# 5_ButtonsAndLeds.net
KiCad netlist of a schematic drawn in Altium Designer
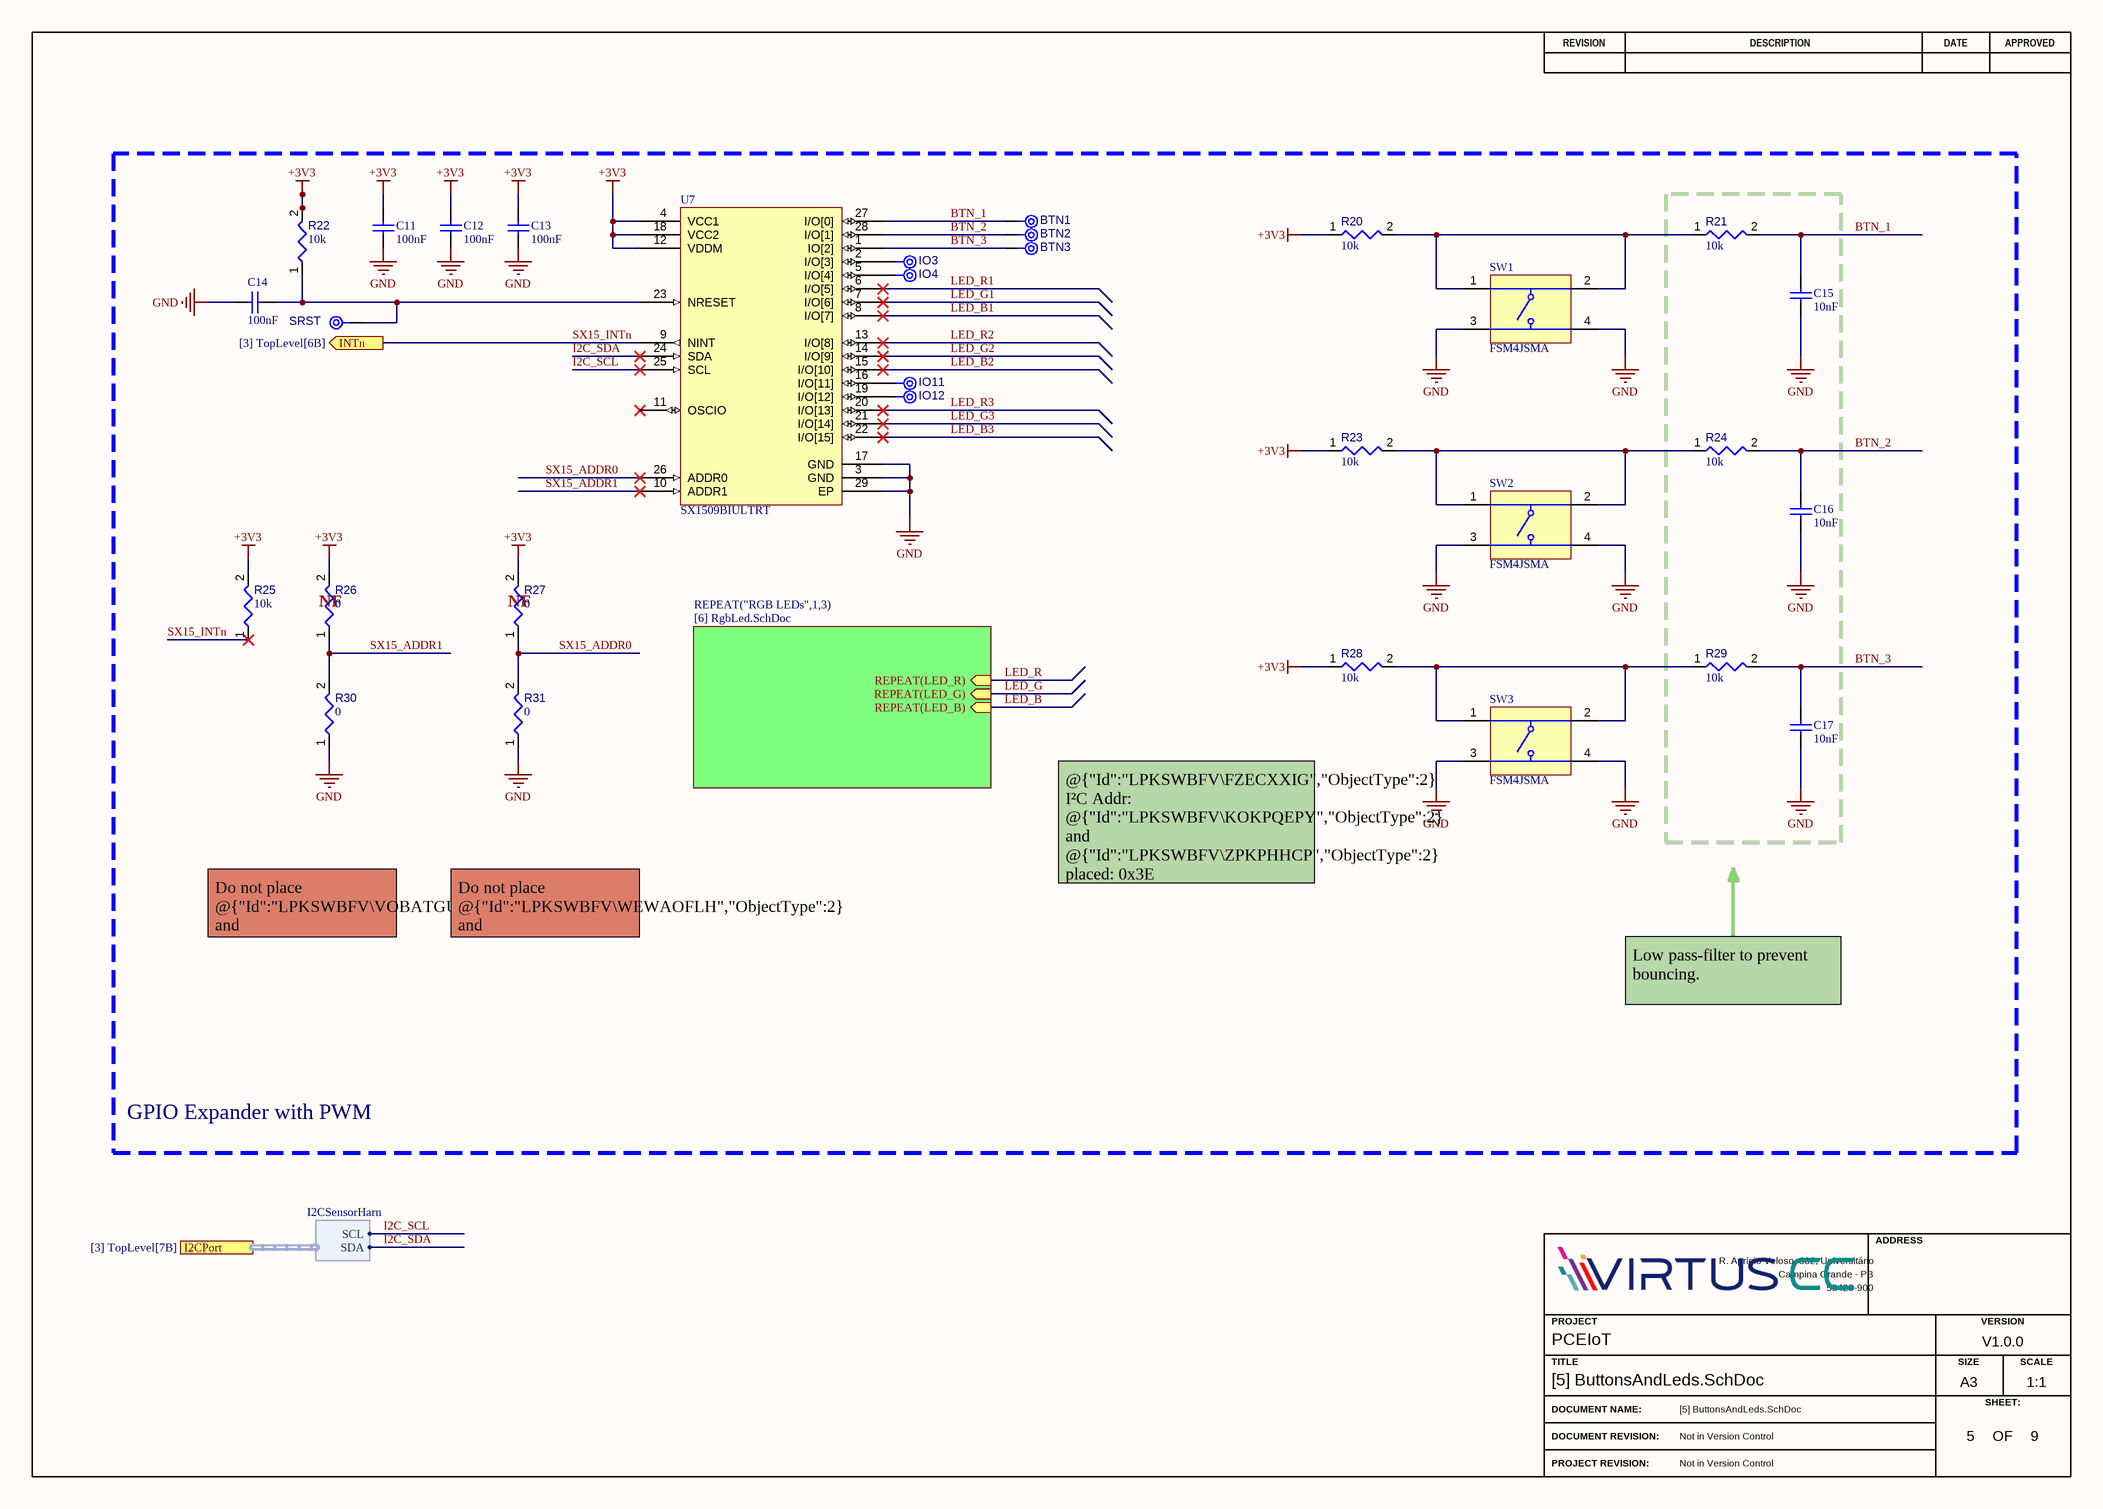
[diagram p0: [5] ButtonsAndLeds.SchDoc]

(export (version "E")
  (design (tool "Eeschema 10.0.6"))
  (components
    (comp (ref "BTN1")
      (value "TPAD6R")
      (footprint "TP06R")
      (description "0.6mm round")
      (libsource (lib "PCEIOT") (part "CMP-00028-00002-2"))
    )
    (comp (ref "BTN2")
      (value "TPAD6R")
      (footprint "TP06R")
      (description "0.6mm round")
      (libsource (lib "PCEIOT") (part "CMP-00028-00002-2"))
    )
    (comp (ref "BTN3")
      (value "TPAD6R")
      (footprint "TP06R")
      (description "0.6mm round")
      (libsource (lib "PCEIOT") (part "CMP-00028-00002-2"))
    )
    (comp (ref "C11")
      (value "100nF")
      (footprint "CAPC0603(1608)100_L")
      (description "Multilayer Ceramic Capacitor, 0.1 uF, 16 V, ± 20%, X7R, 0603 [1608 Metric]")
      (fields (field (name "TOLERANCE") "20%") (field (name "Comment") "VJ0603Y104MXJCW1BC"))
      (libsource (lib "UFCG - Universidade Federal de Campina Grande") (part "CAP"))
    )
    (comp (ref "C12")
      (value "100nF")
      (footprint "CAPC0603(1608)100_L")
      (description "Multilayer Ceramic Capacitor, 0.1 uF, 16 V, ± 20%, X7R, 0603 [1608 Metric]")
      (fields (field (name "TOLERANCE") "20%") (field (name "Comment") "VJ0603Y104MXJCW1BC"))
      (libsource (lib "UFCG - Universidade Federal de Campina Grande") (part "CAP"))
    )
    (comp (ref "C13")
      (value "100nF")
      (footprint "CAPC0603(1608)100_L")
      (description "Multilayer Ceramic Capacitor, 0.1 uF, 16 V, ± 20%, X7R, 0603 [1608 Metric]")
      (fields (field (name "TOLERANCE") "20%") (field (name "Comment") "VJ0603Y104MXJCW1BC"))
      (libsource (lib "UFCG - Universidade Federal de Campina Grande") (part "CAP"))
    )
    (comp (ref "C14")
      (value "100nF")
      (footprint "CAPC0603(1608)100_L")
      (description "Multilayer Ceramic Capacitor, 0.1 uF, 16 V, ± 20%, X7R, 0603 [1608 Metric]")
      (fields (field (name "TOLERANCE") "20%") (field (name "Comment") "VJ0603Y104MXJCW1BC"))
      (libsource (lib "UFCG - Universidade Federal de Campina Grande") (part "CAP"))
    )
    (comp (ref "C15")
      (value "10nF")
      (footprint "CAPC0603(1608)100_L")
      (description "Multilayer Ceramic Capacitor, 0.01 uF, 50 V, ± 10%, X7R, 0603 [1608 Metric]")
      (fields (field (name "VOLTAGE") "50V") (field (name "TOLERANCE") "10%"))
      (libsource (lib "UFCG - Universidade Federal de Campina Grande") (part "CAP"))
    )
    (comp (ref "C16")
      (value "10nF")
      (footprint "CAPC0603(1608)100_L")
      (description "Multilayer Ceramic Capacitor, 0.01 uF, 50 V, ± 10%, X7R, 0603 [1608 Metric]")
      (fields (field (name "VOLTAGE") "50V") (field (name "TOLERANCE") "10%"))
      (libsource (lib "UFCG - Universidade Federal de Campina Grande") (part "CAP"))
    )
    (comp (ref "C17")
      (value "10nF")
      (footprint "CAPC0603(1608)100_L")
      (description "Multilayer Ceramic Capacitor, 0.01 uF, 50 V, ± 10%, X7R, 0603 [1608 Metric]")
      (fields (field (name "VOLTAGE") "50V") (field (name "TOLERANCE") "10%"))
      (libsource (lib "UFCG - Universidade Federal de Campina Grande") (part "CAP"))
    )
    (comp (ref "IO3")
      (value "TPAD6R")
      (footprint "TP06R")
      (description "0.6mm round")
      (libsource (lib "PCEIOT") (part "CMP-00028-00002-2"))
    )
    (comp (ref "IO4")
      (value "TPAD6R")
      (footprint "TP06R")
      (description "0.6mm round")
      (libsource (lib "PCEIOT") (part "CMP-00028-00002-2"))
    )
    (comp (ref "IO11")
      (value "TPAD6R")
      (footprint "TP06R")
      (description "0.6mm round")
      (libsource (lib "PCEIOT") (part "CMP-00028-00002-2"))
    )
    (comp (ref "IO12")
      (value "TPAD6R")
      (footprint "TP06R")
      (description "0.6mm round")
      (libsource (lib "PCEIOT") (part "CMP-00028-00002-2"))
    )
    (comp (ref "R20")
      (value "10k")
      (footprint "RESC0603(1608)_L")
      (description "Chip Resistor, 10 KOhm, +/- 1%, 01 W, -55 to 155 degC, 0603 (1608 Metric)")
      (fields (field (name "POWER") "100mW") (field (name "TOLERANCE") "1%"))
      (libsource (lib "UFCG - Universidade Federal de Campina Grande") (part "RES-2"))
    )
    (comp (ref "R21")
      (value "10k")
      (footprint "RESC0603(1608)_L")
      (description "Chip Resistor, 10 KOhm, +/- 1%, 01 W, -55 to 155 degC, 0603 (1608 Metric)")
      (fields (field (name "POWER") "100mW") (field (name "TOLERANCE") "1%"))
      (libsource (lib "UFCG - Universidade Federal de Campina Grande") (part "RES-2"))
    )
    (comp (ref "R22")
      (value "10k")
      (footprint "RESC0603(1608)_L")
      (description "Chip Resistor, 10 KOhm, +/- 1%, 01 W, -55 to 155 degC, 0603 (1608 Metric)")
      (fields (field (name "POWER") "100mW") (field (name "TOLERANCE") "1%"))
      (libsource (lib "UFCG - Universidade Federal de Campina Grande") (part "RES-2"))
    )
    (comp (ref "R23")
      (value "10k")
      (footprint "RESC0603(1608)_L")
      (description "Chip Resistor, 10 KOhm, +/- 1%, 01 W, -55 to 155 degC, 0603 (1608 Metric)")
      (fields (field (name "POWER") "100mW") (field (name "TOLERANCE") "1%"))
      (libsource (lib "UFCG - Universidade Federal de Campina Grande") (part "RES-2"))
    )
    (comp (ref "R24")
      (value "10k")
      (footprint "RESC0603(1608)_L")
      (description "Chip Resistor, 10 KOhm, +/- 1%, 01 W, -55 to 155 degC, 0603 (1608 Metric)")
      (fields (field (name "POWER") "100mW") (field (name "TOLERANCE") "1%"))
      (libsource (lib "UFCG - Universidade Federal de Campina Grande") (part "RES-2"))
    )
    (comp (ref "R25")
      (value "10k")
      (footprint "RESC0603(1608)_L")
      (description "Chip Resistor, 10 KOhm, +/- 1%, 01 W, -55 to 155 degC, 0603 (1608 Metric)")
      (fields (field (name "POWER") "100mW") (field (name "TOLERANCE") "1%"))
      (libsource (lib "UFCG - Universidade Federal de Campina Grande") (part "RES-2"))
    )
    (comp (ref "R26")
      (value "0")
      (footprint "RESC0603(1608)_L")
      (description "Chip Resistor, 0 Ohm, 0.1 W, -55 to 155 degC, 0603 (1608 Metric)")
      (fields (field (name "TOLERANCE") "5%") (field (name "POWER") "100mW"))
      (libsource (lib "UFCG - Universidade Federal de Campina Grande") (part "RES-2"))
    )
    (comp (ref "R27")
      (value "0")
      (footprint "RESC0603(1608)_L")
      (description "Chip Resistor, 0 Ohm, 0.1 W, -55 to 155 degC, 0603 (1608 Metric)")
      (fields (field (name "TOLERANCE") "5%") (field (name "POWER") "100mW"))
      (libsource (lib "UFCG - Universidade Federal de Campina Grande") (part "RES-2"))
    )
    (comp (ref "R28")
      (value "10k")
      (footprint "RESC0603(1608)_L")
      (description "Chip Resistor, 10 KOhm, +/- 1%, 01 W, -55 to 155 degC, 0603 (1608 Metric)")
      (fields (field (name "POWER") "100mW") (field (name "TOLERANCE") "1%"))
      (libsource (lib "UFCG - Universidade Federal de Campina Grande") (part "RES-2"))
    )
    (comp (ref "R29")
      (value "10k")
      (footprint "RESC0603(1608)_L")
      (description "Chip Resistor, 10 KOhm, +/- 1%, 01 W, -55 to 155 degC, 0603 (1608 Metric)")
      (fields (field (name "POWER") "100mW") (field (name "TOLERANCE") "1%"))
      (libsource (lib "UFCG - Universidade Federal de Campina Grande") (part "RES-2"))
    )
    (comp (ref "R30")
      (value "0")
      (footprint "RESC0603(1608)_L")
      (description "Chip Resistor, 0 Ohm, 0.1 W, -55 to 155 degC, 0603 (1608 Metric)")
      (fields (field (name "TOLERANCE") "5%") (field (name "POWER") "100mW"))
      (libsource (lib "UFCG - Universidade Federal de Campina Grande") (part "RES-2"))
    )
    (comp (ref "R31")
      (value "0")
      (footprint "RESC0603(1608)_L")
      (description "Chip Resistor, 0 Ohm, 0.1 W, -55 to 155 degC, 0603 (1608 Metric)")
      (fields (field (name "TOLERANCE") "5%") (field (name "POWER") "100mW"))
      (libsource (lib "UFCG - Universidade Federal de Campina Grande") (part "RES-2"))
    )
    (comp (ref "SRST")
      (value "TPAD6R")
      (footprint "TP06R")
      (description "0.6mm round")
      (libsource (lib "PCEIOT") (part "CMP-00028-00002-2"))
    )
    (comp (ref "SW1")
      (value "FSM4JSMA")
      (footprint "TECO-FSM4JSMA_V")
      (description "Switch Tactile OFF (ON) SPST Round Button Gull Wing 0.05A 12VDC 1.57N SMD Loose Piece")
      (libsource (lib "UFCG - Universidade Federal de Campina Grande") (part "SW-SPST-4_A"))
    )
    (comp (ref "SW2")
      (value "FSM4JSMA")
      (footprint "TECO-FSM4JSMA_V")
      (description "Switch Tactile OFF (ON) SPST Round Button Gull Wing 0.05A 12VDC 1.57N SMD Loose Piece")
      (libsource (lib "UFCG - Universidade Federal de Campina Grande") (part "SW-SPST-4_A"))
    )
    (comp (ref "SW3")
      (value "FSM4JSMA")
      (footprint "TECO-FSM4JSMA_V")
      (description "Switch Tactile OFF (ON) SPST Round Button Gull Wing 0.05A 12VDC 1.57N SMD Loose Piece")
      (libsource (lib "UFCG - Universidade Federal de Campina Grande") (part "SW-SPST-4_A"))
    )
    (comp (ref "U7")
      (value "SX1509BIULTRT")
      (footprint "QFN40P410X410X60_HS-29N")
      (description "IC Gpio Expander I2C 16CH 28QFN / I2C Interface 5.5V 28-PIN Qfn-ut Ep T/r")
      (libsource (lib "UFCG - Universidade Federal de Campina Grande") (part "New symbol 1"))
    )
  )
  (nets
    (net (code "2") (name "+3V3") (class "Default")
      (node (ref "C11") (pin "2") (pinfunction "2_2") (pintype "passive"))
      (node (ref "C12") (pin "2") (pinfunction "2_2") (pintype "passive"))
      (node (ref "C13") (pin "2") (pinfunction "2_2") (pintype "passive"))
      (node (ref "R20") (pin "1") (pinfunction "1_1") (pintype "passive"))
      (node (ref "R22") (pin "2") (pinfunction "2_2") (pintype "passive"))
      (node (ref "R23") (pin "1") (pinfunction "1_1") (pintype "passive"))
      (node (ref "R25") (pin "2") (pinfunction "2_2") (pintype "passive"))
      (node (ref "R26") (pin "2") (pinfunction "2_2") (pintype "passive"))
      (node (ref "R27") (pin "2") (pinfunction "2_2") (pintype "passive"))
      (node (ref "R28") (pin "1") (pinfunction "1_1") (pintype "passive"))
      (node (ref "U7") (pin "12") (pinfunction "VDDM_12") (pintype "power_in"))
      (node (ref "U7") (pin "18") (pinfunction "VCC2_18") (pintype "power_in"))
      (node (ref "U7") (pin "4") (pinfunction "VCC1_4") (pintype "power_in"))
    )
    (net (code "3") (name "/BTN_1") (class "Default")
      (node (ref "BTN1") (pin "1") (pinfunction "TP_1") (pintype "passive"))
      (node (ref "C15") (pin "2") (pinfunction "2_2") (pintype "passive"))
      (node (ref "R21") (pin "2") (pinfunction "2_2") (pintype "passive"))
      (node (ref "U7") (pin "27") (pinfunction "I/O[0]_27") (pintype "bidirectional"))
    )
    (net (code "4") (name "/BTN_2") (class "Default")
      (node (ref "BTN2") (pin "1") (pinfunction "TP_1") (pintype "passive"))
      (node (ref "C16") (pin "2") (pinfunction "2_2") (pintype "passive"))
      (node (ref "R24") (pin "2") (pinfunction "2_2") (pintype "passive"))
      (node (ref "U7") (pin "28") (pinfunction "I/O[1]_28") (pintype "bidirectional"))
    )
    (net (code "5") (name "/BTN_3") (class "Default")
      (node (ref "BTN3") (pin "1") (pinfunction "TP_1") (pintype "passive"))
      (node (ref "C17") (pin "2") (pinfunction "2_2") (pintype "passive"))
      (node (ref "R29") (pin "2") (pinfunction "2_2") (pintype "passive"))
      (node (ref "U7") (pin "1") (pinfunction "IO[2]_1") (pintype "bidirectional"))
    )
    (net (code "6") (name "/I2C_SCL") (class "Default")
      (node (ref "U7") (pin "25") (pinfunction "SCL_25") (pintype "input+no_connect"))
    )
    (net (code "7") (name "/I2C_SDA") (class "Default")
      (node (ref "U7") (pin "24") (pinfunction "SDA_24") (pintype "input+no_connect"))
    )
    (net (code "9") (name "/LED_B1") (class "Default")
      (node (ref "U7") (pin "8") (pinfunction "I/O[7]_8") (pintype "bidirectional+no_connect"))
    )
    (net (code "10") (name "/LED_B2") (class "Default")
      (node (ref "U7") (pin "15") (pinfunction "I/O[10]_15") (pintype "bidirectional+no_connect"))
    )
    (net (code "11") (name "/LED_B3") (class "Default")
      (node (ref "U7") (pin "22") (pinfunction "I/O[15]_22") (pintype "bidirectional+no_connect"))
    )
    (net (code "13") (name "/LED_G1") (class "Default")
      (node (ref "U7") (pin "7") (pinfunction "I/O[6]_7") (pintype "bidirectional+no_connect"))
    )
    (net (code "14") (name "/LED_G2") (class "Default")
      (node (ref "U7") (pin "14") (pinfunction "I/O[9]_14") (pintype "bidirectional+no_connect"))
    )
    (net (code "15") (name "/LED_G3") (class "Default")
      (node (ref "U7") (pin "21") (pinfunction "I/O[14]_21") (pintype "bidirectional+no_connect"))
    )
    (net (code "17") (name "/LED_R1") (class "Default")
      (node (ref "U7") (pin "6") (pinfunction "I/O[5]_6") (pintype "bidirectional+no_connect"))
    )
    (net (code "18") (name "/LED_R2") (class "Default")
      (node (ref "U7") (pin "13") (pinfunction "I/O[8]_13") (pintype "bidirectional+no_connect"))
    )
    (net (code "19") (name "/LED_R3") (class "Default")
      (node (ref "U7") (pin "20") (pinfunction "I/O[13]_20") (pintype "bidirectional+no_connect"))
    )
    (net (code "20") (name "/SX15_ADDR0") (class "Default")
      (node (ref "R27") (pin "1") (pinfunction "1_1") (pintype "passive"))
      (node (ref "R31") (pin "2") (pinfunction "2_2") (pintype "passive"))
      (node (ref "U7") (pin "26") (pinfunction "ADDR0_26") (pintype "input"))
    )
    (net (code "21") (name "/SX15_ADDR1") (class "Default")
      (node (ref "R26") (pin "1") (pinfunction "1_1") (pintype "passive"))
      (node (ref "R30") (pin "2") (pinfunction "2_2") (pintype "passive"))
      (node (ref "U7") (pin "10") (pinfunction "ADDR1_10") (pintype "input"))
    )
    (net (code "22") (name "/SX15_INTn") (class "Default")
      (node (ref "R25") (pin "1") (pinfunction "1_1") (pintype "passive"))
      (node (ref "U7") (pin "9") (pinfunction "NINT_9") (pintype "output"))
    )
    (net (code "24") (name "GND") (class "Default")
      (node (ref "C11") (pin "1") (pinfunction "1_1") (pintype "passive"))
      (node (ref "C12") (pin "1") (pinfunction "1_1") (pintype "passive"))
      (node (ref "C13") (pin "1") (pinfunction "1_1") (pintype "passive"))
      (node (ref "C14") (pin "1") (pinfunction "1_1") (pintype "passive"))
      (node (ref "C15") (pin "1") (pinfunction "1_1") (pintype "passive"))
      (node (ref "C16") (pin "1") (pinfunction "1_1") (pintype "passive"))
      (node (ref "C17") (pin "1") (pinfunction "1_1") (pintype "passive"))
      (node (ref "R30") (pin "1") (pinfunction "1_1") (pintype "passive"))
      (node (ref "R31") (pin "1") (pinfunction "1_1") (pintype "passive"))
      (node (ref "SW1") (pin "3") (pinfunction "3_3") (pintype "passive"))
      (node (ref "SW1") (pin "4") (pinfunction "4_4") (pintype "passive"))
      (node (ref "SW2") (pin "3") (pinfunction "3_3") (pintype "passive"))
      (node (ref "SW2") (pin "4") (pinfunction "4_4") (pintype "passive"))
      (node (ref "SW3") (pin "3") (pinfunction "3_3") (pintype "passive"))
      (node (ref "SW3") (pin "4") (pinfunction "4_4") (pintype "passive"))
      (node (ref "U7") (pin "17") (pinfunction "GND_17") (pintype "power_in"))
      (node (ref "U7") (pin "29") (pinfunction "EP_29") (pintype "power_in"))
      (node (ref "U7") (pin "3") (pinfunction "GND_3") (pintype "power_in"))
    )
    (net (code "25") (name "Net-(IO3-TP)") (class "Default")
      (node (ref "IO3") (pin "1") (pinfunction "TP_1") (pintype "passive"))
      (node (ref "U7") (pin "2") (pinfunction "I/O[3]_2") (pintype "bidirectional"))
    )
    (net (code "26") (name "Net-(IO4-TP)") (class "Default")
      (node (ref "IO4") (pin "1") (pinfunction "TP_1") (pintype "passive"))
      (node (ref "U7") (pin "5") (pinfunction "I/O[4]_5") (pintype "bidirectional"))
    )
    (net (code "27") (name "Net-(IO11-TP)") (class "Default")
      (node (ref "IO11") (pin "1") (pinfunction "TP_1") (pintype "passive"))
      (node (ref "U7") (pin "16") (pinfunction "I/O[11]_16") (pintype "bidirectional"))
    )
    (net (code "28") (name "Net-(IO12-TP)") (class "Default")
      (node (ref "IO12") (pin "1") (pinfunction "TP_1") (pintype "passive"))
      (node (ref "U7") (pin "19") (pinfunction "I/O[12]_19") (pintype "bidirectional"))
    )
    (net (code "29") (name "Net-(R20-Pad2)") (class "Default")
      (node (ref "R20") (pin "2") (pinfunction "2_2") (pintype "passive"))
      (node (ref "R21") (pin "1") (pinfunction "1_1") (pintype "passive"))
      (node (ref "SW1") (pin "1") (pinfunction "1_1") (pintype "passive"))
      (node (ref "SW1") (pin "2") (pinfunction "2_2") (pintype "passive"))
    )
    (net (code "30") (name "Net-(R23-Pad2)") (class "Default")
      (node (ref "R23") (pin "2") (pinfunction "2_2") (pintype "passive"))
      (node (ref "R24") (pin "1") (pinfunction "1_1") (pintype "passive"))
      (node (ref "SW2") (pin "1") (pinfunction "1_1") (pintype "passive"))
      (node (ref "SW2") (pin "2") (pinfunction "2_2") (pintype "passive"))
    )
    (net (code "31") (name "Net-(R28-Pad2)") (class "Default")
      (node (ref "R28") (pin "2") (pinfunction "2_2") (pintype "passive"))
      (node (ref "R29") (pin "1") (pinfunction "1_1") (pintype "passive"))
      (node (ref "SW3") (pin "1") (pinfunction "1_1") (pintype "passive"))
      (node (ref "SW3") (pin "2") (pinfunction "2_2") (pintype "passive"))
    )
    (net (code "32") (name "Net-(SRST-TP)") (class "Default")
      (node (ref "C14") (pin "2") (pinfunction "2_2") (pintype "passive"))
      (node (ref "R22") (pin "1") (pinfunction "1_1") (pintype "passive"))
      (node (ref "SRST") (pin "1") (pinfunction "TP_1") (pintype "passive"))
      (node (ref "U7") (pin "23") (pinfunction "NRESET_23") (pintype "input"))
    )
    (net (code "33") (name "unconnected-(U7-OSCIO-Pad11)") (class "Default")
      (node (ref "U7") (pin "11") (pinfunction "OSCIO_11") (pintype "bidirectional+no_connect"))
    )
  )
)
